# 4x6.net
KiCad netlist of a schematic drawn in Altium Designer
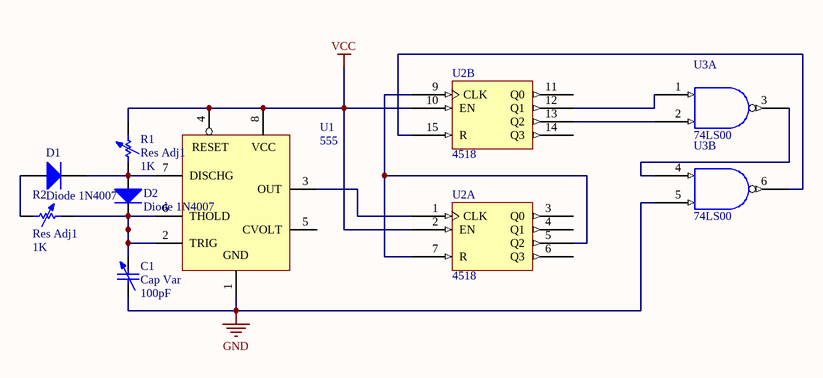
[diagram p0: 4x6.SchDoc]

(export (version "E")
  (design (tool "Eeschema 10.0.6"))
  (components
    (comp (ref "C1")
      (value "Cap Var")
      (footprint "C1210_N")
      (description "Variable or Adjustable Capacitor")
      (fields (field (name "ALTIUM_VALUE") "100pF") (field (name "PUBLISHER") "Altium Limited"))
      (libsource (lib "Miscellaneous Devices") (part "Cap Var"))
    )
    (comp (ref "D1")
      (value "Diode 1N4007")
      (footprint "DO-41")
      (description "1 Amp General Purpose Rectifier")
      (fields (field (name "PUBLISHER") "Altium Limited"))
      (libsource (lib "Miscellaneous Devices") (part "Diode 1N4007"))
    )
    (comp (ref "D2")
      (value "Diode 1N4007")
      (footprint "DO-41")
      (description "1 Amp General Purpose Rectifier")
      (fields (field (name "PUBLISHER") "Altium Limited"))
      (libsource (lib "Miscellaneous Devices") (part "Diode 1N4007"))
    )
    (comp (ref "R1")
      (value "Res Adj1")
      (footprint "AXIAL-0.7")
      (description "Variable Resistor")
      (fields (field (name "ALTIUM_VALUE") "1K") (field (name "PUBLISHER") "Altium Limited"))
      (libsource (lib "Miscellaneous Devices") (part "Res Adj1"))
    )
    (comp (ref "R2")
      (value "Res Adj1")
      (footprint "AXIAL-0.7")
      (description "Variable Resistor")
      (fields (field (name "ALTIUM_VALUE") "1K") (field (name "PUBLISHER") "Altium Limited"))
      (libsource (lib "Miscellaneous Devices") (part "Res Adj1"))
    )
    (comp (ref "U1") (value "555") (description "Timer") (libsource (lib "555") (part "555")))
    (comp (ref "U2") (value "4518") (footprint "DIP-16") (libsource (lib "CD4000系列IC") (part "4518")))
    (comp (ref "U3") (value "74LS00") (footprint "DIP-14") (libsource (lib "TTL74系列IC") (part "74LS00")))
  )
  (nets
    (net (code "1") (name "GND") (class "Default")
      (node (ref "C1") (pin "1") (pinfunction "1_1") (pintype "passive"))
      (node (ref "U1") (pin "1") (pinfunction "GND_1") (pintype "passive"))
      (node (ref "U2") (pin "8") (pinfunction "GND_8") (pintype "power_in"))
      (node (ref "U3") (pin "5") (pintype "input"))
      (node (ref "U3") (pin "7") (pinfunction "GND_7") (pintype "power_in"))
    )
    (net (code "2") (name "Net-(D1-A)") (class "Default")
      (node (ref "D1") (pin "1") (pinfunction "A_1") (pintype "passive"))
      (node (ref "R2") (pin "1") (pinfunction "1_1") (pintype "passive"))
    )
    (net (code "3") (name "Net-(D1-K)") (class "Default")
      (node (ref "D1") (pin "2") (pinfunction "K_2") (pintype "passive"))
      (node (ref "R1") (pin "1") (pinfunction "1_1") (pintype "passive"))
      (node (ref "U1") (pin "7") (pinfunction "DISCHG_7") (pintype "passive"))
    )
    (net (code "4") (name "Net-(D2-K)") (class "Default")
      (node (ref "C1") (pin "2") (pinfunction "2_2") (pintype "passive"))
      (node (ref "D2") (pin "2") (pinfunction "K_2") (pintype "passive"))
      (node (ref "R2") (pin "2") (pinfunction "2_2") (pintype "passive"))
      (node (ref "U1") (pin "2") (pinfunction "TRIG_2") (pintype "passive"))
      (node (ref "U1") (pin "6") (pinfunction "THOLD_6") (pintype "passive"))
    )
    (net (code "5") (name "Net-(U1-OUT)") (class "Default")
      (node (ref "U1") (pin "3") (pinfunction "OUT_3") (pintype "passive"))
      (node (ref "U2") (pin "1") (pinfunction "CLK_1") (pintype "input"))
    )
    (net (code "6") (name "Net-(U2A-Q2)") (class "Default")
      (node (ref "U2") (pin "5") (pinfunction "Q2_5") (pintype "output"))
      (node (ref "U2") (pin "7") (pinfunction "R_7") (pintype "input"))
      (node (ref "U2") (pin "9") (pinfunction "CLK_9") (pintype "input"))
    )
    (net (code "7") (name "Net-(U2B-Q1)") (class "Default")
      (node (ref "U2") (pin "12") (pinfunction "Q1_12") (pintype "output"))
      (node (ref "U3") (pin "1") (pintype "input"))
    )
    (net (code "8") (name "Net-(U2B-Q2)") (class "Default")
      (node (ref "U2") (pin "13") (pinfunction "Q2_13") (pintype "output"))
      (node (ref "U3") (pin "2") (pintype "input"))
    )
    (net (code "9") (name "Net-(U2B-R)") (class "Default")
      (node (ref "U2") (pin "15") (pinfunction "R_15") (pintype "input"))
      (node (ref "U3") (pin "6") (pintype "output"))
    )
    (net (code "10") (name "Net-(U3-Pad3)") (class "Default")
      (node (ref "U3") (pin "3") (pintype "output"))
      (node (ref "U3") (pin "4") (pintype "input"))
    )
    (net (code "11") (name "VCC") (class "Default")
      (node (ref "R1") (pin "2") (pinfunction "2_2") (pintype "passive"))
      (node (ref "U1") (pin "4") (pinfunction "RESET_4") (pintype "passive"))
      (node (ref "U1") (pin "8") (pinfunction "VCC_8") (pintype "passive"))
      (node (ref "U2") (pin "10") (pinfunction "EN_10") (pintype "input"))
      (node (ref "U2") (pin "16") (pinfunction "VCC_16") (pintype "power_in"))
      (node (ref "U2") (pin "2") (pinfunction "EN_2") (pintype "input"))
      (node (ref "U3") (pin "14") (pinfunction "VCC_14") (pintype "power_in"))
    )
    (net (code "12") (name "unconnected-(D2-A-Pad1)") (class "Default")
      (node (ref "D2") (pin "1") (pinfunction "A_1") (pintype "passive"))
    )
    (net (code "13") (name "unconnected-(U1-CVOLT-Pad5)") (class "Default")
      (node (ref "U1") (pin "5") (pinfunction "CVOLT_5") (pintype "passive"))
    )
    (net (code "14") (name "unconnected-(U2A-Q0-Pad3)") (class "Default")
      (node (ref "U2") (pin "3") (pinfunction "Q0_3") (pintype "output"))
    )
    (net (code "15") (name "unconnected-(U2A-Q1-Pad4)") (class "Default")
      (node (ref "U2") (pin "4") (pinfunction "Q1_4") (pintype "output"))
    )
    (net (code "16") (name "unconnected-(U2A-Q3-Pad6)") (class "Default")
      (node (ref "U2") (pin "6") (pinfunction "Q3_6") (pintype "output"))
    )
    (net (code "17") (name "unconnected-(U2B-Q0-Pad11)") (class "Default")
      (node (ref "U2") (pin "11") (pinfunction "Q0_11") (pintype "output"))
    )
    (net (code "18") (name "unconnected-(U2B-Q3-Pad14)") (class "Default")
      (node (ref "U2") (pin "14") (pinfunction "Q3_14") (pintype "output"))
    )
  )
)
